# Channel.net
KiCad netlist of a schematic drawn in Altium Designer
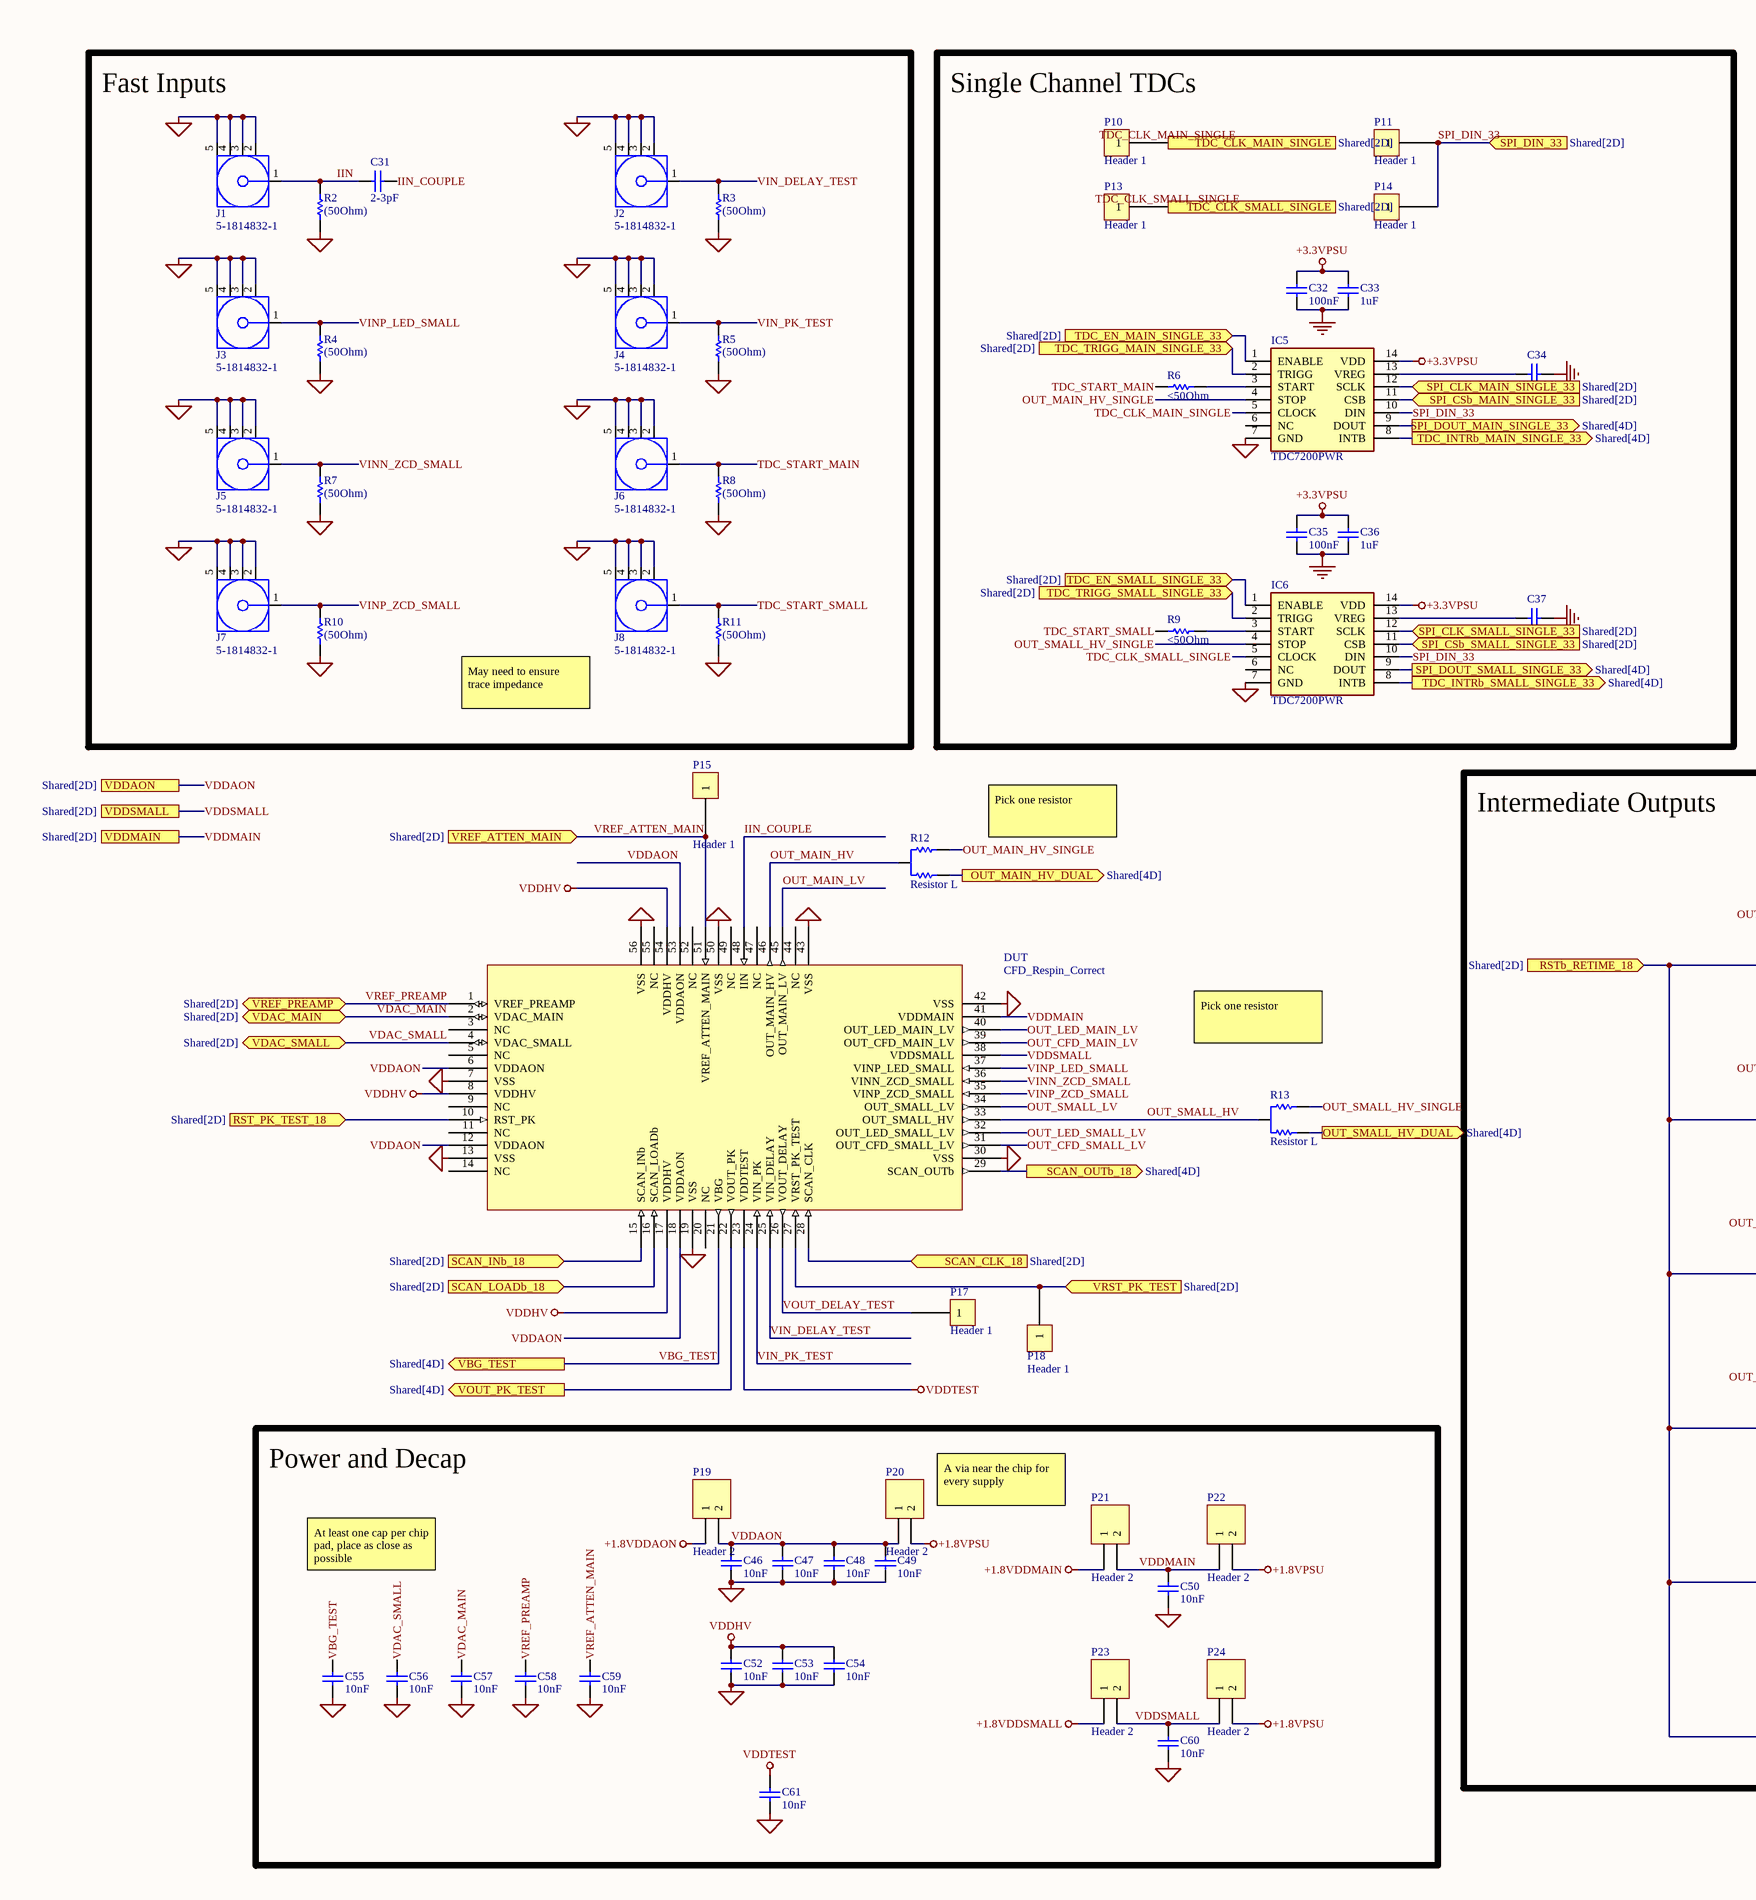
[diagram p0: Channel.SchDoc, left]
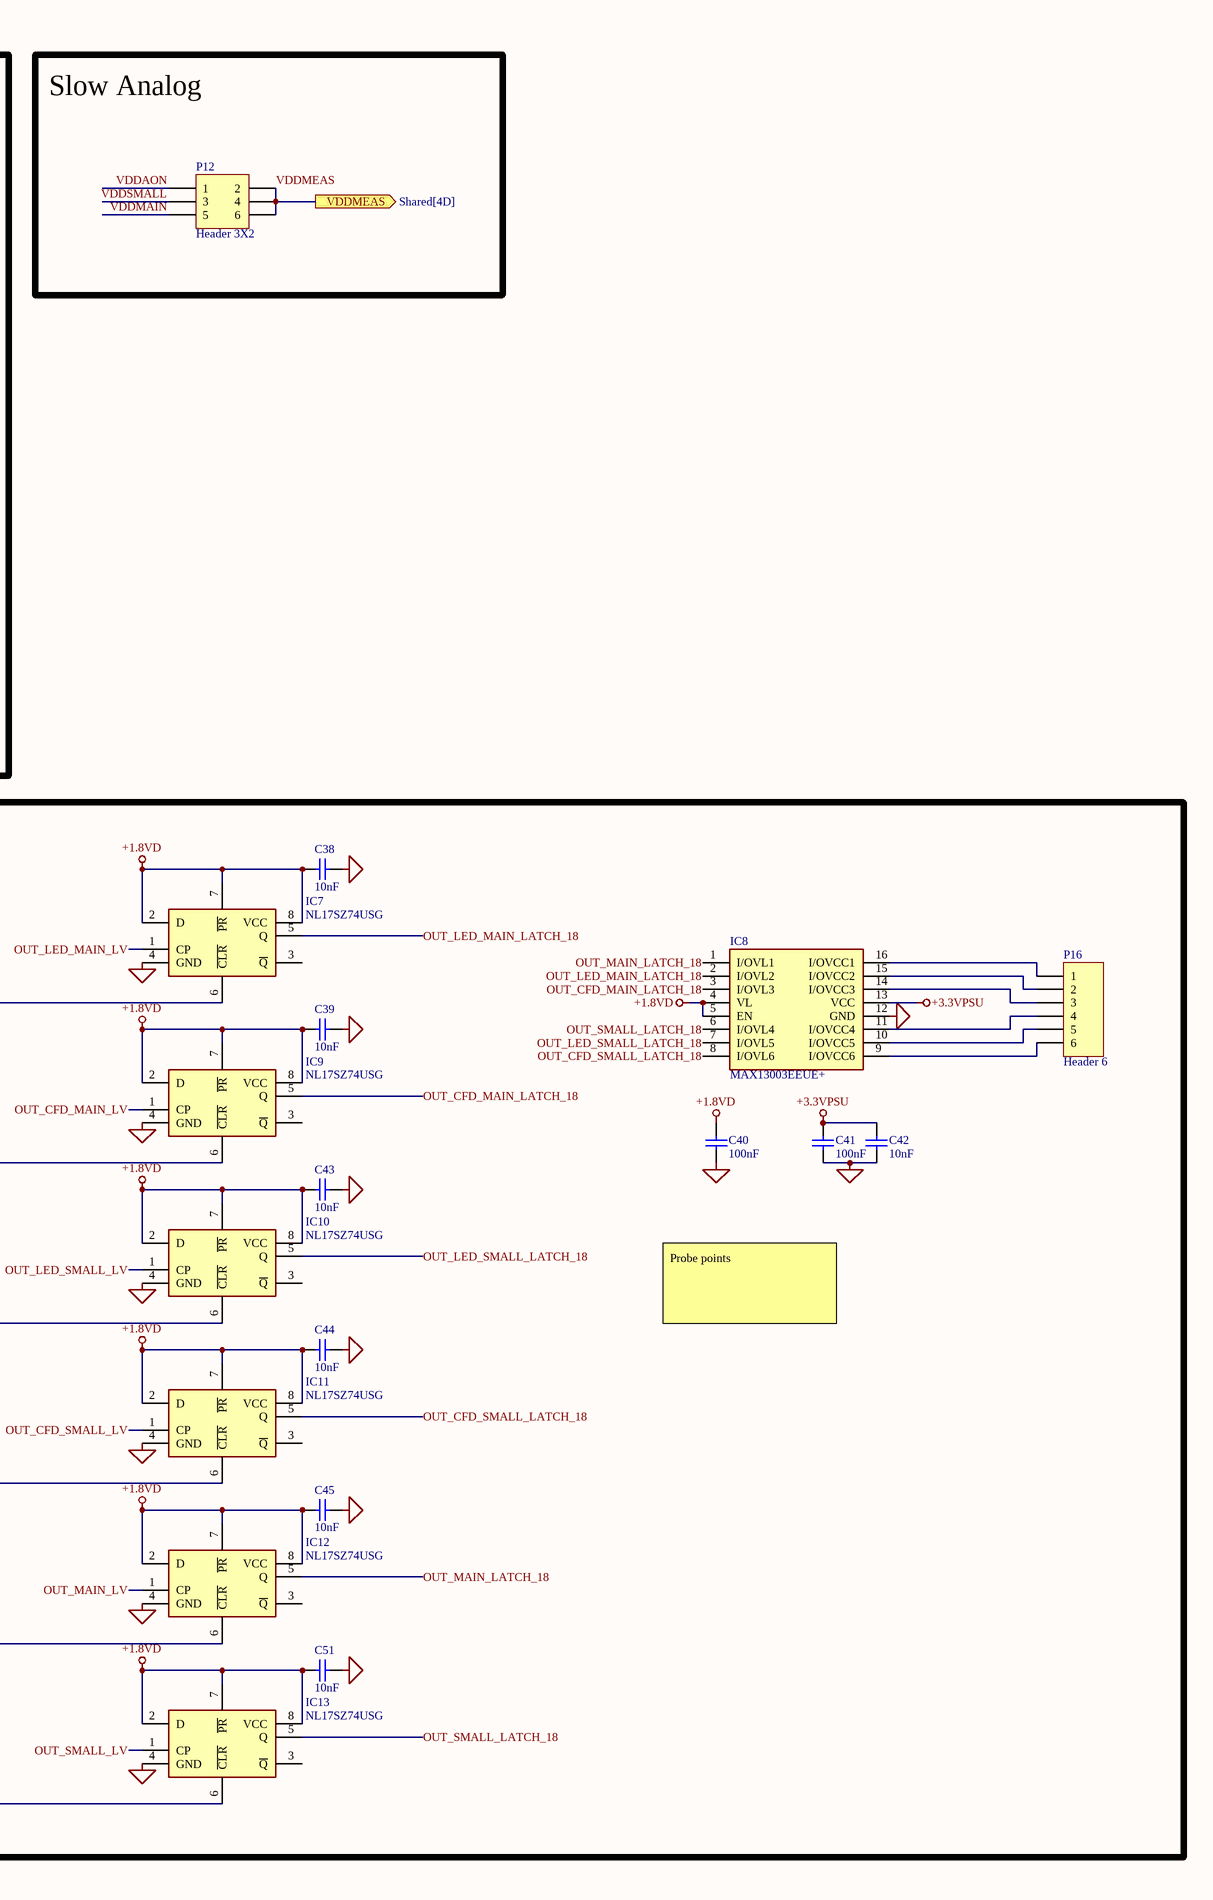
[diagram p1: Channel.SchDoc, right]

(export (version "E")
  (design (tool "Eeschema 10.0.6"))
  (components
    (comp (ref "C31")
      (value "2-3pF")
      (footprint "CAPC1608X90X35ML10T15")
      (description "0603,2-3pF")
      (fields (field (name "MANUFACTURER") "Murata"))
      (libsource (lib "Altium Content Vault") (part "CAP-NP-2"))
    )
    (comp (ref "C32")
      (value "100nF")
      (footprint "CAPC1608X90X35ML10T15")
      (description "0603,100nF")
      (fields (field (name "MANUFACTURER") "Murata"))
      (libsource (lib "Altium Content Vault") (part "CAP-NP-2"))
    )
    (comp (ref "C33")
      (value "1uF")
      (footprint "CAPC1608X90X35ML10T15")
      (description "0603,1uF")
      (fields (field (name "MANUFACTURER") "Murata"))
      (libsource (lib "Altium Content Vault") (part "CAP-NP-2"))
    )
    (comp (ref "C34")
      (value "1uF")
      (footprint "CAPC1608X90X35ML10T15")
      (description "0603,1uF")
      (fields (field (name "MANUFACTURER") "Murata"))
      (libsource (lib "Altium Content Vault") (part "CAP-NP-2"))
    )
    (comp (ref "C35")
      (value "100nF")
      (footprint "CAPC1608X90X35ML10T15")
      (description "0603,100nF")
      (fields (field (name "MANUFACTURER") "Murata"))
      (libsource (lib "Altium Content Vault") (part "CAP-NP-2"))
    )
    (comp (ref "C36")
      (value "1uF")
      (footprint "CAPC1608X90X35ML10T15")
      (description "0603,1uF")
      (fields (field (name "MANUFACTURER") "Murata"))
      (libsource (lib "Altium Content Vault") (part "CAP-NP-2"))
    )
    (comp (ref "C37")
      (value "1uF")
      (footprint "CAPC1608X90X35ML10T15")
      (description "0603,1uF")
      (fields (field (name "MANUFACTURER") "Murata"))
      (libsource (lib "Altium Content Vault") (part "CAP-NP-2"))
    )
    (comp (ref "C38")
      (value "10nF")
      (footprint "CAPC1608X90X35ML10T15")
      (description "0603,10nF")
      (fields (field (name "MANUFACTURER") "Murata"))
      (libsource (lib "Altium Content Vault") (part "CAP-NP-2"))
    )
    (comp (ref "C39")
      (value "10nF")
      (footprint "CAPC1608X90X35ML10T15")
      (description "0603,10nF")
      (fields (field (name "MANUFACTURER") "Murata"))
      (libsource (lib "Altium Content Vault") (part "CAP-NP-2"))
    )
    (comp (ref "C40")
      (value "100nF")
      (footprint "CAPC1608X90X35ML10T15")
      (description "0603,100nF")
      (fields (field (name "MANUFACTURER") "Murata"))
      (libsource (lib "Altium Content Vault") (part "CAP-NP-2"))
    )
    (comp (ref "C41")
      (value "100nF")
      (footprint "CAPC1608X90X35ML10T15")
      (description "0603,100nF")
      (fields (field (name "MANUFACTURER") "Murata"))
      (libsource (lib "Altium Content Vault") (part "CAP-NP-2"))
    )
    (comp (ref "C42")
      (value "10nF")
      (footprint "CAPC1608X90X35ML10T15")
      (description "0603,10nF")
      (fields (field (name "MANUFACTURER") "Murata"))
      (libsource (lib "Altium Content Vault") (part "CAP-NP-2"))
    )
    (comp (ref "C43")
      (value "10nF")
      (footprint "CAPC1608X90X35ML10T15")
      (description "0603,10nF")
      (fields (field (name "MANUFACTURER") "Murata"))
      (libsource (lib "Altium Content Vault") (part "CAP-NP-2"))
    )
    (comp (ref "C44")
      (value "10nF")
      (footprint "CAPC1608X90X35ML10T15")
      (description "0603,10nF")
      (fields (field (name "MANUFACTURER") "Murata"))
      (libsource (lib "Altium Content Vault") (part "CAP-NP-2"))
    )
    (comp (ref "C45")
      (value "10nF")
      (footprint "CAPC1608X90X35ML10T15")
      (description "0603,10nF")
      (fields (field (name "MANUFACTURER") "Murata"))
      (libsource (lib "Altium Content Vault") (part "CAP-NP-2"))
    )
    (comp (ref "C46")
      (value "10nF")
      (footprint "CAPC1608X90X35ML10T15")
      (description "0603,10nF")
      (fields (field (name "MANUFACTURER") "Murata"))
      (libsource (lib "Altium Content Vault") (part "CAP-NP-2"))
    )
    (comp (ref "C47")
      (value "10nF")
      (footprint "CAPC1608X90X35ML10T15")
      (description "0603,10nF")
      (fields (field (name "MANUFACTURER") "Murata"))
      (libsource (lib "Altium Content Vault") (part "CAP-NP-2"))
    )
    (comp (ref "C48")
      (value "10nF")
      (footprint "CAPC1608X90X35ML10T15")
      (description "0603,10nF")
      (fields (field (name "MANUFACTURER") "Murata"))
      (libsource (lib "Altium Content Vault") (part "CAP-NP-2"))
    )
    (comp (ref "C49")
      (value "10nF")
      (footprint "CAPC1608X90X35ML10T15")
      (description "0603,10nF")
      (fields (field (name "MANUFACTURER") "Murata"))
      (libsource (lib "Altium Content Vault") (part "CAP-NP-2"))
    )
    (comp (ref "C50")
      (value "10nF")
      (footprint "CAPC1608X90X35ML10T15")
      (description "0603,10nF")
      (fields (field (name "MANUFACTURER") "Murata"))
      (libsource (lib "Altium Content Vault") (part "CAP-NP-2"))
    )
    (comp (ref "C51")
      (value "10nF")
      (footprint "CAPC1608X90X35ML10T15")
      (description "0603,10nF")
      (fields (field (name "MANUFACTURER") "Murata"))
      (libsource (lib "Altium Content Vault") (part "CAP-NP-2"))
    )
    (comp (ref "C52")
      (value "10nF")
      (footprint "CAPC1608X90X35ML10T15")
      (description "0603,10nF")
      (fields (field (name "MANUFACTURER") "Murata"))
      (libsource (lib "Altium Content Vault") (part "CAP-NP-2"))
    )
    (comp (ref "C53")
      (value "10nF")
      (footprint "CAPC1608X90X35ML10T15")
      (description "0603,10nF")
      (fields (field (name "MANUFACTURER") "Murata"))
      (libsource (lib "Altium Content Vault") (part "CAP-NP-2"))
    )
    (comp (ref "C54")
      (value "10nF")
      (footprint "CAPC1608X90X35ML10T15")
      (description "0603,10nF")
      (fields (field (name "MANUFACTURER") "Murata"))
      (libsource (lib "Altium Content Vault") (part "CAP-NP-2"))
    )
    (comp (ref "C55")
      (value "10nF")
      (footprint "CAPC1608X90X35ML10T15")
      (description "0603,10nF")
      (fields (field (name "MANUFACTURER") "Murata"))
      (libsource (lib "Altium Content Vault") (part "CAP-NP-2"))
    )
    (comp (ref "C56")
      (value "10nF")
      (footprint "CAPC1608X90X35ML10T15")
      (description "0603,10nF")
      (fields (field (name "MANUFACTURER") "Murata"))
      (libsource (lib "Altium Content Vault") (part "CAP-NP-2"))
    )
    (comp (ref "C57")
      (value "10nF")
      (footprint "CAPC1608X90X35ML10T15")
      (description "0603,10nF")
      (fields (field (name "MANUFACTURER") "Murata"))
      (libsource (lib "Altium Content Vault") (part "CAP-NP-2"))
    )
    (comp (ref "C58")
      (value "10nF")
      (footprint "CAPC1608X90X35ML10T15")
      (description "0603,10nF")
      (fields (field (name "MANUFACTURER") "Murata"))
      (libsource (lib "Altium Content Vault") (part "CAP-NP-2"))
    )
    (comp (ref "C59")
      (value "10nF")
      (footprint "CAPC1608X90X35ML10T15")
      (description "0603,10nF")
      (fields (field (name "MANUFACTURER") "Murata"))
      (libsource (lib "Altium Content Vault") (part "CAP-NP-2"))
    )
    (comp (ref "C60")
      (value "10nF")
      (footprint "CAPC1608X90X35ML10T15")
      (description "0603,10nF")
      (fields (field (name "MANUFACTURER") "Murata"))
      (libsource (lib "Altium Content Vault") (part "CAP-NP-2"))
    )
    (comp (ref "C61")
      (value "10nF")
      (footprint "CAPC1608X90X35ML10T15")
      (description "0603,10nF")
      (fields (field (name "MANUFACTURER") "Murata"))
      (libsource (lib "Altium Content Vault") (part "CAP-NP-2"))
    )
    (comp (ref "DUT")
      (value "CFD_Respin_Correct")
      (footprint "QFN50P800X800X80_HS-57N_WIDEVIAS")
      (libsource (lib "intlib") (part "CFD_Respin_Correct"))
    )
    (comp (ref "IC5")
      (value "TDC7200PWR")
      (footprint "SamacSys:SOP65P640X120-14N")
      (description "Integrated Circuit")
      (libsource (lib "*") (part "TDC7200PWR"))
    )
    (comp (ref "IC6")
      (value "TDC7200PWR")
      (footprint "SamacSys:SOP65P640X120-14N")
      (description "Integrated Circuit")
      (libsource (lib "*") (part "TDC7200PWR"))
    )
    (comp (ref "IC7")
      (value "NL17SZ74USG")
      (footprint "SamacSys:SOP50P310X90-8N")
      (description "Flip Flops 1.65-5.5V CMOS Single D-Type")
      (libsource (lib "SamacSys") (part "NL17SZ74USG"))
    )
    (comp (ref "IC8")
      (value "MAX13003EEUE+")
      (footprint "SamacSys:SOP65P640X110-16N")
      (description "Integrated Circuit")
      (libsource (lib "*") (part "MAX13003EEUE+"))
    )
    (comp (ref "IC9")
      (value "NL17SZ74USG")
      (footprint "SamacSys:SOP50P310X90-8N")
      (description "Flip Flops 1.65-5.5V CMOS Single D-Type")
      (libsource (lib "SamacSys") (part "NL17SZ74USG"))
    )
    (comp (ref "IC10")
      (value "NL17SZ74USG")
      (footprint "SamacSys:SOP50P310X90-8N")
      (description "Flip Flops 1.65-5.5V CMOS Single D-Type")
      (libsource (lib "SamacSys") (part "NL17SZ74USG"))
    )
    (comp (ref "IC11")
      (value "NL17SZ74USG")
      (footprint "SamacSys:SOP50P310X90-8N")
      (description "Flip Flops 1.65-5.5V CMOS Single D-Type")
      (libsource (lib "SamacSys") (part "NL17SZ74USG"))
    )
    (comp (ref "IC12")
      (value "NL17SZ74USG")
      (footprint "SamacSys:SOP50P310X90-8N")
      (description "Flip Flops 1.65-5.5V CMOS Single D-Type")
      (libsource (lib "SamacSys") (part "NL17SZ74USG"))
    )
    (comp (ref "IC13")
      (value "NL17SZ74USG")
      (footprint "SamacSys:SOP50P310X90-8N")
      (description "Flip Flops 1.65-5.5V CMOS Single D-Type")
      (libsource (lib "SamacSys") (part "NL17SZ74USG"))
    )
    (comp (ref "J1")
      (value "5-1814832-1")
      (footprint "TECO-5-1814832-1_V")
      (fields (field (name "MANUFACTURER") "TE Connectivity"))
      (libsource (lib "Altium Content Vault") (part "CN-S-4F-RF5"))
    )
    (comp (ref "J2")
      (value "5-1814832-1")
      (footprint "TECO-5-1814832-1_V")
      (fields (field (name "MANUFACTURER") "TE Connectivity"))
      (libsource (lib "Altium Content Vault") (part "CN-S-4F-RF5"))
    )
    (comp (ref "J3")
      (value "5-1814832-1")
      (footprint "TECO-5-1814832-1_V")
      (fields (field (name "MANUFACTURER") "TE Connectivity"))
      (libsource (lib "Altium Content Vault") (part "CN-S-4F-RF5"))
    )
    (comp (ref "J4")
      (value "5-1814832-1")
      (footprint "TECO-5-1814832-1_V")
      (fields (field (name "MANUFACTURER") "TE Connectivity"))
      (libsource (lib "Altium Content Vault") (part "CN-S-4F-RF5"))
    )
    (comp (ref "J5")
      (value "5-1814832-1")
      (footprint "TECO-5-1814832-1_V")
      (fields (field (name "MANUFACTURER") "TE Connectivity"))
      (libsource (lib "Altium Content Vault") (part "CN-S-4F-RF5"))
    )
    (comp (ref "J6")
      (value "5-1814832-1")
      (footprint "TECO-5-1814832-1_V")
      (fields (field (name "MANUFACTURER") "TE Connectivity"))
      (libsource (lib "Altium Content Vault") (part "CN-S-4F-RF5"))
    )
    (comp (ref "J7")
      (value "5-1814832-1")
      (footprint "TECO-5-1814832-1_V")
      (fields (field (name "MANUFACTURER") "TE Connectivity"))
      (libsource (lib "Altium Content Vault") (part "CN-S-4F-RF5"))
    )
    (comp (ref "J8")
      (value "5-1814832-1")
      (footprint "TECO-5-1814832-1_V")
      (fields (field (name "MANUFACTURER") "TE Connectivity"))
      (libsource (lib "Altium Content Vault") (part "CN-S-4F-RF5"))
    )
    (comp (ref "P10") (value "Header 1") (footprint "Header1") (libsource (lib "") (part "Header 1_1")))
    (comp (ref "P11") (value "Header 1") (footprint "Header1") (libsource (lib "") (part "Header 1_1")))
    (comp (ref "P12")
      (value "Header 3X2")
      (footprint "HDR2X3")
      (description "Header, 3-Pin, Dual row")
      (fields (field (name "PUBLISHER") "Altium Limited"))
      (libsource (lib "Miscellaneous Connectors") (part "Header 3X2"))
    )
    (comp (ref "P13") (value "Header 1") (footprint "Header1") (libsource (lib "") (part "Header 1_1")))
    (comp (ref "P14") (value "Header 1") (footprint "Header1") (libsource (lib "") (part "Header 1_1")))
    (comp (ref "P15") (value "Header 1") (footprint "Header1") (libsource (lib "") (part "Header 1_3")))
    (comp (ref "P16")
      (value "Header 6")
      (footprint "HDR1X6")
      (description "Header, 6-Pin")
      (fields (field (name "PUBLISHER") "Altium Limited"))
      (libsource (lib "Miscellaneous Connectors") (part "Header 6"))
    )
    (comp (ref "P17") (value "Header 1") (footprint "Header1") (libsource (lib "") (part "Header 1_2")))
    (comp (ref "P18") (value "Header 1") (footprint "Header1") (libsource (lib "intlib") (part "Header 1")))
    (comp (ref "P19")
      (value "Header 2")
      (footprint "HDR1X2")
      (description "Header, 2-Pin")
      (fields (field (name "PUBLISHER") "Altium Limited"))
      (libsource (lib "Miscellaneous Connectors") (part "Header 2"))
    )
    (comp (ref "P20")
      (value "Header 2")
      (footprint "HDR1X2")
      (description "Header, 2-Pin")
      (fields (field (name "PUBLISHER") "Altium Limited"))
      (libsource (lib "Miscellaneous Connectors") (part "Header 2"))
    )
    (comp (ref "P21")
      (value "Header 2")
      (footprint "HDR1X2")
      (description "Header, 2-Pin")
      (fields (field (name "PUBLISHER") "Altium Limited"))
      (libsource (lib "Miscellaneous Connectors") (part "Header 2"))
    )
    (comp (ref "P22")
      (value "Header 2")
      (footprint "HDR1X2")
      (description "Header, 2-Pin")
      (fields (field (name "PUBLISHER") "Altium Limited"))
      (libsource (lib "Miscellaneous Connectors") (part "Header 2"))
    )
    (comp (ref "P23")
      (value "Header 2")
      (footprint "HDR1X2")
      (description "Header, 2-Pin")
      (fields (field (name "PUBLISHER") "Altium Limited"))
      (libsource (lib "Miscellaneous Connectors") (part "Header 2"))
    )
    (comp (ref "P24")
      (value "Header 2")
      (footprint "HDR1X2")
      (description "Header, 2-Pin")
      (fields (field (name "PUBLISHER") "Altium Limited"))
      (libsource (lib "Miscellaneous Connectors") (part "Header 2"))
    )
    (comp (ref "R2")
      (value "(50Ohm)")
      (footprint "RESC1609X50X30NL8T20")
      (description "0603,(50Ohm),Do Not Populate")
      (fields (field (name "MANUFACTURER") "Vishay Semiconductor"))
      (libsource (lib "Altium Content Vault") (part "RES-2"))
    )
    (comp (ref "R3")
      (value "(50Ohm)")
      (footprint "RESC1609X50X30NL8T20")
      (description "0603,(50Ohm),Do Not Populate")
      (fields (field (name "MANUFACTURER") "Vishay Semiconductor"))
      (libsource (lib "Altium Content Vault") (part "RES-2"))
    )
    (comp (ref "R4")
      (value "(50Ohm)")
      (footprint "RESC1609X50X30NL8T20")
      (description "0603,(50Ohm),Do Not Populate")
      (fields (field (name "MANUFACTURER") "Vishay Semiconductor"))
      (libsource (lib "Altium Content Vault") (part "RES-2"))
    )
    (comp (ref "R5")
      (value "(50Ohm)")
      (footprint "RESC1609X50X30NL8T20")
      (description "0603,(50Ohm),Do Not Populate")
      (fields (field (name "MANUFACTURER") "Vishay Semiconductor"))
      (libsource (lib "Altium Content Vault") (part "RES-2"))
    )
    (comp (ref "R6")
      (value "<50Ohm")
      (footprint "RESC1609X50X30NL8T20")
      (description "0603,<50Ohm")
      (fields (field (name "MANUFACTURER") "Vishay Semiconductor"))
      (libsource (lib "Altium Content Vault") (part "RES-2"))
    )
    (comp (ref "R7")
      (value "(50Ohm)")
      (footprint "RESC1609X50X30NL8T20")
      (description "0603,(50Ohm),Do Not Populate")
      (fields (field (name "MANUFACTURER") "Vishay Semiconductor"))
      (libsource (lib "Altium Content Vault") (part "RES-2"))
    )
    (comp (ref "R8")
      (value "(50Ohm)")
      (footprint "RESC1609X50X30NL8T20")
      (description "0603,(50Ohm),Do Not Populate")
      (fields (field (name "MANUFACTURER") "Vishay Semiconductor"))
      (libsource (lib "Altium Content Vault") (part "RES-2"))
    )
    (comp (ref "R9")
      (value "<50Ohm")
      (footprint "RESC1609X50X30NL8T20")
      (description "0603,<50Ohm")
      (fields (field (name "MANUFACTURER") "Vishay Semiconductor"))
      (libsource (lib "Altium Content Vault") (part "RES-2"))
    )
    (comp (ref "R10")
      (value "(50Ohm)")
      (footprint "RESC1609X50X30NL8T20")
      (description "0603,(50Ohm),Do Not Populate")
      (fields (field (name "MANUFACTURER") "Vishay Semiconductor"))
      (libsource (lib "Altium Content Vault") (part "RES-2"))
    )
    (comp (ref "R11")
      (value "(50Ohm)")
      (footprint "RESC1609X50X30NL8T20")
      (description "0603,(50Ohm),Do Not Populate")
      (fields (field (name "MANUFACTURER") "Vishay Semiconductor"))
      (libsource (lib "Altium Content Vault") (part "RES-2"))
    )
    (comp (ref "R12")
      (value "Resistor L")
      (footprint "RESL")
      (description "Pick one 0603,0Ohm")
      (libsource (lib "intlib") (part "Resistor L"))
    )
    (comp (ref "R13")
      (value "Resistor L")
      (footprint "RESL")
      (description "Pick one 0603,0Ohm")
      (libsource (lib "intlib") (part "Resistor L"))
    )
  )
  (nets
    (net (code "1") (name "+1.8VD") (class "Default")
      (node (ref "C38") (pin "2") (pinfunction "2_2") (pintype "passive"))
      (node (ref "C39") (pin "2") (pinfunction "2_2") (pintype "passive"))
      (node (ref "C40") (pin "2") (pinfunction "2_2") (pintype "passive"))
      (node (ref "C43") (pin "2") (pinfunction "2_2") (pintype "passive"))
      (node (ref "C44") (pin "2") (pinfunction "2_2") (pintype "passive"))
      (node (ref "C45") (pin "2") (pinfunction "2_2") (pintype "passive"))
      (node (ref "C51") (pin "2") (pinfunction "2_2") (pintype "passive"))
      (node (ref "IC10") (pin "2") (pinfunction "D_2") (pintype "passive"))
      (node (ref "IC10") (pin "7") (pinfunction "~{PR}_7") (pintype "passive"))
      (node (ref "IC10") (pin "8") (pinfunction "VCC_8") (pintype "passive"))
      (node (ref "IC11") (pin "2") (pinfunction "D_2") (pintype "passive"))
      (node (ref "IC11") (pin "7") (pinfunction "~{PR}_7") (pintype "passive"))
      (node (ref "IC11") (pin "8") (pinfunction "VCC_8") (pintype "passive"))
      (node (ref "IC12") (pin "2") (pinfunction "D_2") (pintype "passive"))
      (node (ref "IC12") (pin "7") (pinfunction "~{PR}_7") (pintype "passive"))
      (node (ref "IC12") (pin "8") (pinfunction "VCC_8") (pintype "passive"))
      (node (ref "IC13") (pin "2") (pinfunction "D_2") (pintype "passive"))
      (node (ref "IC13") (pin "7") (pinfunction "~{PR}_7") (pintype "passive"))
      (node (ref "IC13") (pin "8") (pinfunction "VCC_8") (pintype "passive"))
      (node (ref "IC7") (pin "2") (pinfunction "D_2") (pintype "passive"))
      (node (ref "IC7") (pin "7") (pinfunction "~{PR}_7") (pintype "passive"))
      (node (ref "IC7") (pin "8") (pinfunction "VCC_8") (pintype "passive"))
      (node (ref "IC8") (pin "4") (pinfunction "VL_4") (pintype "passive"))
      (node (ref "IC8") (pin "5") (pinfunction "EN_5") (pintype "passive"))
      (node (ref "IC9") (pin "2") (pinfunction "D_2") (pintype "passive"))
      (node (ref "IC9") (pin "7") (pinfunction "~{PR}_7") (pintype "passive"))
      (node (ref "IC9") (pin "8") (pinfunction "VCC_8") (pintype "passive"))
    )
    (net (code "2") (name "+1.8VDDAON") (class "Default")
      (node (ref "P19") (pin "1") (pinfunction "1_1") (pintype "passive"))
    )
    (net (code "3") (name "+1.8VDDMAIN") (class "Default")
      (node (ref "P21") (pin "1") (pinfunction "1_1") (pintype "passive"))
    )
    (net (code "4") (name "+1.8VDDSMALL") (class "Default")
      (node (ref "P23") (pin "1") (pinfunction "1_1") (pintype "passive"))
    )
    (net (code "5") (name "+1.8VPSU") (class "Default")
      (node (ref "P20") (pin "2") (pinfunction "2_2") (pintype "passive"))
      (node (ref "P22") (pin "2") (pinfunction "2_2") (pintype "passive"))
      (node (ref "P24") (pin "2") (pinfunction "2_2") (pintype "passive"))
    )
    (net (code "6") (name "+3.3VPSU") (class "Default")
      (node (ref "C32") (pin "1") (pinfunction "1_1") (pintype "passive"))
      (node (ref "C33") (pin "1") (pinfunction "1_1") (pintype "passive"))
      (node (ref "C35") (pin "1") (pinfunction "1_1") (pintype "passive"))
      (node (ref "C36") (pin "1") (pinfunction "1_1") (pintype "passive"))
      (node (ref "C41") (pin "2") (pinfunction "2_2") (pintype "passive"))
      (node (ref "C42") (pin "2") (pinfunction "2_2") (pintype "passive"))
      (node (ref "IC5") (pin "14") (pinfunction "VDD_14") (pintype "passive"))
      (node (ref "IC6") (pin "14") (pinfunction "VDD_14") (pintype "passive"))
      (node (ref "IC8") (pin "13") (pinfunction "VCC_13") (pintype "passive"))
    )
    (net (code "7") (name "/IIN") (class "Default")
      (node (ref "C31") (pin "1") (pinfunction "1_1") (pintype "passive"))
      (node (ref "J1") (pin "1") (pinfunction "1_1") (pintype "passive"))
      (node (ref "R2") (pin "2") (pinfunction "2_2") (pintype "passive"))
    )
    (net (code "8") (name "/IIN_COUPLE") (class "Default")
      (node (ref "C31") (pin "2") (pinfunction "2_2") (pintype "passive"))
      (node (ref "DUT") (pin "48") (pinfunction "IIN_48") (pintype "input"))
    )
    (net (code "9") (name "/OUT_CFD_MAIN_LATCH_18") (class "Default")
      (node (ref "IC8") (pin "3") (pinfunction "I/OVL3_3") (pintype "passive"))
      (node (ref "IC9") (pin "5") (pinfunction "Q_5") (pintype "passive"))
    )
    (net (code "10") (name "/OUT_CFD_MAIN_LV") (class "Default")
      (node (ref "DUT") (pin "39") (pinfunction "OUT_CFD_MAIN_LV_39") (pintype "output"))
      (node (ref "IC9") (pin "1") (pinfunction "CP_1") (pintype "passive"))
    )
    (net (code "11") (name "/OUT_CFD_SMALL_LATCH_18") (class "Default")
      (node (ref "IC11") (pin "5") (pinfunction "Q_5") (pintype "passive"))
      (node (ref "IC8") (pin "8") (pinfunction "I/OVL6_8") (pintype "passive"))
    )
    (net (code "12") (name "/OUT_CFD_SMALL_LV") (class "Default")
      (node (ref "DUT") (pin "31") (pinfunction "OUT_CFD_SMALL_LV_31") (pintype "output"))
      (node (ref "IC11") (pin "1") (pinfunction "CP_1") (pintype "passive"))
    )
    (net (code "13") (name "/OUT_LED_MAIN_LATCH_18") (class "Default")
      (node (ref "IC7") (pin "5") (pinfunction "Q_5") (pintype "passive"))
      (node (ref "IC8") (pin "2") (pinfunction "I/OVL2_2") (pintype "passive"))
    )
    (net (code "14") (name "/OUT_LED_MAIN_LV") (class "Default")
      (node (ref "DUT") (pin "40") (pinfunction "OUT_LED_MAIN_LV_40") (pintype "output"))
      (node (ref "IC7") (pin "1") (pinfunction "CP_1") (pintype "passive"))
    )
    (net (code "15") (name "/OUT_LED_SMALL_LATCH_18") (class "Default")
      (node (ref "IC10") (pin "5") (pinfunction "Q_5") (pintype "passive"))
      (node (ref "IC8") (pin "7") (pinfunction "I/OVL5_7") (pintype "passive"))
    )
    (net (code "16") (name "/OUT_LED_SMALL_LV") (class "Default")
      (node (ref "DUT") (pin "32") (pinfunction "OUT_LED_SMALL_LV_32") (pintype "output"))
      (node (ref "IC10") (pin "1") (pinfunction "CP_1") (pintype "passive"))
    )
    (net (code "17") (name "/OUT_MAIN_HV") (class "Default")
      (node (ref "DUT") (pin "46") (pinfunction "OUT_MAIN_HV_46") (pintype "output"))
      (node (ref "R12") (pin "1") (pinfunction "1_1") (pintype "passive"))
    )
    (net (code "18") (name "/OUT_MAIN_HV_DUAL") (class "Default")
      (node (ref "R12") (pin "2") (pinfunction "2_2") (pintype "passive"))
    )
    (net (code "19") (name "/OUT_MAIN_HV_SINGLE") (class "Default")
      (node (ref "IC5") (pin "4") (pinfunction "STOP_4") (pintype "passive"))
      (node (ref "R12") (pin "3") (pinfunction "3_3") (pintype "passive"))
    )
    (net (code "20") (name "/OUT_MAIN_LATCH_18") (class "Default")
      (node (ref "IC12") (pin "5") (pinfunction "Q_5") (pintype "passive"))
      (node (ref "IC8") (pin "1") (pinfunction "I/OVL1_1") (pintype "passive"))
    )
    (net (code "21") (name "/OUT_MAIN_LV") (class "Default")
      (node (ref "DUT") (pin "45") (pinfunction "OUT_MAIN_LV_45") (pintype "output"))
      (node (ref "IC12") (pin "1") (pinfunction "CP_1") (pintype "passive"))
    )
    (net (code "22") (name "/OUT_SMALL_HV") (class "Default")
      (node (ref "DUT") (pin "33") (pinfunction "OUT_SMALL_HV_33") (pintype "output"))
      (node (ref "R13") (pin "1") (pinfunction "1_1") (pintype "passive"))
    )
    (net (code "23") (name "/OUT_SMALL_HV_DUAL") (class "Default")
      (node (ref "R13") (pin "2") (pinfunction "2_2") (pintype "passive"))
    )
    (net (code "24") (name "/OUT_SMALL_HV_SINGLE") (class "Default")
      (node (ref "IC6") (pin "4") (pinfunction "STOP_4") (pintype "passive"))
      (node (ref "R13") (pin "3") (pinfunction "3_3") (pintype "passive"))
    )
    (net (code "25") (name "/OUT_SMALL_LATCH_18") (class "Default")
      (node (ref "IC13") (pin "5") (pinfunction "Q_5") (pintype "passive"))
      (node (ref "IC8") (pin "6") (pinfunction "I/OVL4_6") (pintype "passive"))
    )
    (net (code "26") (name "/OUT_SMALL_LV") (class "Default")
      (node (ref "DUT") (pin "34") (pinfunction "OUT_SMALL_LV_34") (pintype "output"))
      (node (ref "IC13") (pin "1") (pinfunction "CP_1") (pintype "passive"))
    )
    (net (code "27") (name "/RST_PK_TEST_18") (class "Default")
      (node (ref "DUT") (pin "10") (pinfunction "RST_PK_10") (pintype "input"))
    )
    (net (code "28") (name "/RSTb_RETIME_18") (class "Default")
      (node (ref "IC10") (pin "6") (pinfunction "~{CLR}_6") (pintype "passive"))
      (node (ref "IC11") (pin "6") (pinfunction "~{CLR}_6") (pintype "passive"))
      (node (ref "IC12") (pin "6") (pinfunction "~{CLR}_6") (pintype "passive"))
      (node (ref "IC13") (pin "6") (pinfunction "~{CLR}_6") (pintype "passive"))
      (node (ref "IC7") (pin "6") (pinfunction "~{CLR}_6") (pintype "passive"))
      (node (ref "IC9") (pin "6") (pinfunction "~{CLR}_6") (pintype "passive"))
    )
    (net (code "29") (name "/SCAN_CLK_18") (class "Default")
      (node (ref "DUT") (pin "28") (pinfunction "SCAN_CLK_28") (pintype "input"))
    )
    (net (code "30") (name "/SCAN_INb_18") (class "Default")
      (node (ref "DUT") (pin "15") (pinfunction "SCAN_INb_15") (pintype "input"))
    )
    (net (code "31") (name "/SCAN_LOADb_18") (class "Default")
      (node (ref "DUT") (pin "16") (pinfunction "SCAN_LOADb_16") (pintype "input"))
    )
    (net (code "32") (name "/SCAN_OUTb_18") (class "Default")
      (node (ref "DUT") (pin "29") (pinfunction "SCAN_OUTb_29") (pintype "output"))
    )
    (net (code "33") (name "/SPI_CLK_MAIN_SINGLE_33") (class "Default")
      (node (ref "IC5") (pin "12") (pinfunction "SCLK_12") (pintype "passive"))
    )
    (net (code "34") (name "/SPI_CLK_SMALL_SINGLE_33") (class "Default")
      (node (ref "IC6") (pin "12") (pinfunction "SCLK_12") (pintype "passive"))
    )
    (net (code "35") (name "/SPI_CSb_MAIN_SINGLE_33") (class "Default")
      (node (ref "IC5") (pin "11") (pinfunction "CSB_11") (pintype "passive"))
    )
    (net (code "36") (name "/SPI_CSb_SMALL_SINGLE_33") (class "Default")
      (node (ref "IC6") (pin "11") (pinfunction "CSB_11") (pintype "passive"))
    )
    (net (code "37") (name "/SPI_DIN_33") (class "Default")
      (node (ref "IC5") (pin "10") (pinfunction "DIN_10") (pintype "passive"))
      (node (ref "IC6") (pin "10") (pinfunction "DIN_10") (pintype "passive"))
      (node (ref "P11") (pin "1") (pinfunction "1_1") (pintype "passive"))
      (node (ref "P14") (pin "1") (pinfunction "1_1") (pintype "passive"))
    )
    (net (code "38") (name "/SPI_DOUT_MAIN_SINGLE_33") (class "Default")
      (node (ref "IC5") (pin "9") (pinfunction "DOUT_9") (pintype "passive"))
    )
    (net (code "39") (name "/SPI_DOUT_SMALL_SINGLE_33") (class "Default")
      (node (ref "IC6") (pin "9") (pinfunction "DOUT_9") (pintype "passive"))
    )
    (net (code "40") (name "/TDC_CLK_MAIN_SINGLE") (class "Default")
      (node (ref "IC5") (pin "5") (pinfunction "CLOCK_5") (pintype "passive"))
      (node (ref "P10") (pin "1") (pinfunction "1_1") (pintype "passive"))
    )
    (net (code "41") (name "/TDC_CLK_SMALL_SINGLE") (class "Default")
      (node (ref "IC6") (pin "5") (pinfunction "CLOCK_5") (pintype "passive"))
      (node (ref "P13") (pin "1") (pinfunction "1_1") (pintype "passive"))
    )
    (net (code "42") (name "/TDC_EN_MAIN_SINGLE_33") (class "Default")
      (node (ref "IC5") (pin "1") (pinfunction "ENABLE_1") (pintype "passive"))
    )
    (net (code "43") (name "/TDC_EN_SMALL_SINGLE_33") (class "Default")
      (node (ref "IC6") (pin "1") (pinfunction "ENABLE_1") (pintype "passive"))
    )
    (net (code "44") (name "/TDC_INTRb_MAIN_SINGLE_33") (class "Default")
      (node (ref "IC5") (pin "8") (pinfunction "INTB_8") (pintype "passive"))
    )
    (net (code "45") (name "/TDC_INTRb_SMALL_SINGLE_33") (class "Default")
      (node (ref "IC6") (pin "8") (pinfunction "INTB_8") (pintype "passive"))
    )
    (net (code "46") (name "/TDC_START_MAIN") (class "Default")
      (node (ref "J6") (pin "1") (pinfunction "1_1") (pintype "passive"))
      (node (ref "R6") (pin "1") (pinfunction "1_1") (pintype "passive"))
      (node (ref "R8") (pin "2") (pinfunction "2_2") (pintype "passive"))
    )
    (net (code "47") (name "/TDC_START_SMALL") (class "Default")
      (node (ref "J8") (pin "1") (pinfunction "1_1") (pintype "passive"))
      (node (ref "R11") (pin "2") (pinfunction "2_2") (pintype "passive"))
      (node (ref "R9") (pin "1") (pinfunction "1_1") (pintype "passive"))
    )
    (net (code "48") (name "/TDC_TRIGG_MAIN_SINGLE_33") (class "Default")
      (node (ref "IC5") (pin "2") (pinfunction "TRIGG_2") (pintype "passive"))
    )
    (net (code "49") (name "/TDC_TRIGG_SMALL_SINGLE_33") (class "Default")
      (node (ref "IC6") (pin "2") (pinfunction "TRIGG_2") (pintype "passive"))
    )
    (net (code "50") (name "/VBG_TEST") (class "Default")
      (node (ref "C55") (pin "2") (pinfunction "2_2") (pintype "passive"))
      (node (ref "DUT") (pin "21") (pinfunction "VBG_21") (pintype "output"))
    )
    (net (code "51") (name "/VDAC_MAIN") (class "Default")
      (node (ref "C57") (pin "2") (pinfunction "2_2") (pintype "passive"))
      (node (ref "DUT") (pin "2") (pinfunction "VDAC_MAIN_2") (pintype "bidirectional"))
    )
    (net (code "52") (name "/VDAC_SMALL") (class "Default")
      (node (ref "C56") (pin "2") (pinfunction "2_2") (pintype "passive"))
      (node (ref "DUT") (pin "4") (pinfunction "VDAC_SMALL_4") (pintype "bidirectional"))
    )
    (net (code "53") (name "/VDDAON") (class "Default")
      (node (ref "C46") (pin "2") (pinfunction "2_2") (pintype "passive"))
      (node (ref "C47") (pin "2") (pinfunction "2_2") (pintype "passive"))
      (node (ref "C48") (pin "2") (pinfunction "2_2") (pintype "passive"))
      (node (ref "C49") (pin "2") (pinfunction "2_2") (pintype "passive"))
      (node (ref "DUT") (pin "12") (pinfunction "VDDAON_12") (pintype "power_in"))
      (node (ref "DUT") (pin "18") (pinfunction "VDDAON_18") (pintype "power_in"))
      (node (ref "DUT") (pin "53") (pinfunction "VDDAON_53") (pintype "power_in"))
      (node (ref "DUT") (pin "6") (pinfunction "VDDAON_6") (pintype "power_in"))
      (node (ref "P12") (pin "1") (pinfunction "1_1") (pintype "passive"))
      (node (ref "P19") (pin "2") (pinfunction "2_2") (pintype "passive"))
      (node (ref "P20") (pin "1") (pinfunction "1_1") (pintype "passive"))
    )
    (net (code "54") (name "/VDDMAIN") (class "Default")
      (node (ref "C50") (pin "2") (pinfunction "2_2") (pintype "passive"))
      (node (ref "DUT") (pin "41") (pinfunction "VDDMAIN_41") (pintype "power_in"))
      (node (ref "P12") (pin "5") (pinfunction "5_5") (pintype "passive"))
      (node (ref "P21") (pin "2") (pinfunction "2_2") (pintype "passive"))
      (node (ref "P22") (pin "1") (pinfunction "1_1") (pintype "passive"))
    )
    (net (code "55") (name "/VDDMEAS") (class "Default")
      (node (ref "P12") (pin "2") (pinfunction "2_2") (pintype "passive"))
      (node (ref "P12") (pin "4") (pinfunction "4_4") (pintype "passive"))
      (node (ref "P12") (pin "6") (pinfunction "6_6") (pintype "passive"))
    )
    (net (code "56") (name "/VDDSMALL") (class "Default")
      (node (ref "C60") (pin "2") (pinfunction "2_2") (pintype "passive"))
      (node (ref "DUT") (pin "38") (pinfunction "VDDSMALL_38") (pintype "power_in"))
      (node (ref "P12") (pin "3") (pinfunction "3_3") (pintype "passive"))
      (node (ref "P23") (pin "2") (pinfunction "2_2") (pintype "passive"))
      (node (ref "P24") (pin "1") (pinfunction "1_1") (pintype "passive"))
    )
    (net (code "57") (name "/VINN_ZCD_SMALL") (class "Default")
      (node (ref "DUT") (pin "36") (pinfunction "VINN_ZCD_SMALL_36") (pintype "input"))
      (node (ref "J5") (pin "1") (pinfunction "1_1") (pintype "passive"))
      (node (ref "R7") (pin "2") (pinfunction "2_2") (pintype "passive"))
    )
    (net (code "58") (name "/VINP_LED_SMALL") (class "Default")
      (node (ref "DUT") (pin "37") (pinfunction "VINP_LED_SMALL_37") (pintype "input"))
      (node (ref "J3") (pin "1") (pinfunction "1_1") (pintype "passive"))
      (node (ref "R4") (pin "2") (pinfunction "2_2") (pintype "passive"))
    )
    (net (code "59") (name "/VINP_ZCD_SMALL") (class "Default")
      (node (ref "DUT") (pin "35") (pinfunction "VINP_ZCD_SMALL_35") (pintype "input"))
      (node (ref "J7") (pin "1") (pinfunction "1_1") (pintype "passive"))
      (node (ref "R10") (pin "2") (pinfunction "2_2") (pintype "passive"))
    )
    (net (code "60") (name "/VIN_DELAY_TEST") (class "Default")
      (node (ref "DUT") (pin "25") (pinfunction "VIN_DELAY_25") (pintype "input"))
      (node (ref "J2") (pin "1") (pinfunction "1_1") (pintype "passive"))
      (node (ref "R3") (pin "2") (pinfunction "2_2") (pintype "passive"))
    )
    (net (code "61") (name "/VIN_PK_TEST") (class "Default")
      (node (ref "DUT") (pin "24") (pinfunction "VIN_PK_24") (pintype "input"))
      (node (ref "J4") (pin "1") (pinfunction "1_1") (pintype "passive"))
      (node (ref "R5") (pin "2") (pinfunction "2_2") (pintype "passive"))
    )
    (net (code "62") (name "/VOUT_DELAY_TEST") (class "Default")
      (node (ref "DUT") (pin "26") (pinfunction "VOUT_DELAY_26") (pintype "output"))
      (node (ref "P17") (pin "1") (pinfunction "1_1") (pintype "passive"))
    )
    (net (code "63") (name "/VOUT_PK_TEST") (class "Default")
      (node (ref "DUT") (pin "22") (pinfunction "VOUT_PK_22") (pintype "output"))
    )
    (net (code "64") (name "/VREF_ATTEN_MAIN") (class "Default")
      (node (ref "C59") (pin "2") (pinfunction "2_2") (pintype "passive"))
      (node (ref "DUT") (pin "51") (pinfunction "VREF_ATTEN_MAIN_51") (pintype "input"))
      (node (ref "P15") (pin "1") (pinfunction "1_1") (pintype "passive"))
    )
    (net (code "65") (name "/VREF_PREAMP") (class "Default")
      (node (ref "C58") (pin "2") (pinfunction "2_2") (pintype "passive"))
      (node (ref "DUT") (pin "1") (pinfunction "VREF_PREAMP_1") (pintype "bidirectional"))
    )
    (net (code "66") (name "/VRST_PK_TEST") (class "Default")
      (node (ref "DUT") (pin "27") (pinfunction "VRST_PK_TEST_27") (pintype "input"))
      (node (ref "P18") (pin "1") (pinfunction "1_1") (pintype "passive"))
    )
    (net (code "67") (name "GND") (class "Default")
      (node (ref "C32") (pin "2") (pinfunction "2_2") (pintype "passive"))
      (node (ref "C33") (pin "2") (pinfunction "2_2") (pintype "passive"))
      (node (ref "C34") (pin "2") (pinfunction "2_2") (pintype "passive"))
      (node (ref "C35") (pin "2") (pinfunction "2_2") (pintype "passive"))
      (node (ref "C36") (pin "2") (pinfunction "2_2") (pintype "passive"))
      (node (ref "C37") (pin "2") (pinfunction "2_2") (pintype "passive"))
      (node (ref "C38") (pin "1") (pinfunction "1_1") (pintype "passive"))
      (node (ref "C39") (pin "1") (pinfunction "1_1") (pintype "passive"))
      (node (ref "C40") (pin "1") (pinfunction "1_1") (pintype "passive"))
      (node (ref "C41") (pin "1") (pinfunction "1_1") (pintype "passive"))
      (node (ref "C42") (pin "1") (pinfunction "1_1") (pintype "passive"))
      (node (ref "C43") (pin "1") (pinfunction "1_1") (pintype "passive"))
      (node (ref "C44") (pin "1") (pinfunction "1_1") (pintype "passive"))
      (node (ref "C45") (pin "1") (pinfunction "1_1") (pintype "passive"))
      (node (ref "C46") (pin "1") (pinfunction "1_1") (pintype "passive"))
      (node (ref "C47") (pin "1") (pinfunction "1_1") (pintype "passive"))
      (node (ref "C48") (pin "1") (pinfunction "1_1") (pintype "passive"))
      (node (ref "C49") (pin "1") (pinfunction "1_1") (pintype "passive"))
      (node (ref "C50") (pin "1") (pinfunction "1_1") (pintype "passive"))
      (node (ref "C51") (pin "1") (pinfunction "1_1") (pintype "passive"))
      (node (ref "C52") (pin "1") (pinfunction "1_1") (pintype "passive"))
      (node (ref "C53") (pin "1") (pinfunction "1_1") (pintype "passive"))
      (node (ref "C54") (pin "1") (pinfunction "1_1") (pintype "passive"))
      (node (ref "C55") (pin "1") (pinfunction "1_1") (pintype "passive"))
      (node (ref "C56") (pin "1") (pinfunction "1_1") (pintype "passive"))
      (node (ref "C57") (pin "1") (pinfunction "1_1") (pintype "passive"))
      (node (ref "C58") (pin "1") (pinfunction "1_1") (pintype "passive"))
      (node (ref "C59") (pin "1") (pinfunction "1_1") (pintype "passive"))
      (node (ref "C60") (pin "1") (pinfunction "1_1") (pintype "passive"))
      (node (ref "C61") (pin "1") (pinfunction "1_1") (pintype "passive"))
      (node (ref "DUT") (pin "13") (pinfunction "VSS_13") (pintype "power_in"))
      (node (ref "DUT") (pin "19") (pinfunction "VSS_19") (pintype "power_in"))
      (node (ref "DUT") (pin "30") (pinfunction "VSS_30") (pintype "power_in"))
      (node (ref "DUT") (pin "42") (pinfunction "VSS_42") (pintype "power_in"))
      (node (ref "DUT") (pin "43") (pinfunction "VSS_43") (pintype "power_in"))
      (node (ref "DUT") (pin "50") (pinfunction "VSS_50") (pintype "power_in"))
      (node (ref "DUT") (pin "56") (pinfunction "VSS_56") (pintype "power_in"))
      (node (ref "DUT") (pin "7") (pinfunction "VSS_7") (pintype "power_in"))
      (node (ref "IC10") (pin "4") (pinfunction "GND_4") (pintype "passive"))
      (node (ref "IC11") (pin "4") (pinfunction "GND_4") (pintype "passive"))
      (node (ref "IC12") (pin "4") (pinfunction "GND_4") (pintype "passive"))
      (node (ref "IC13") (pin "4") (pinfunction "GND_4") (pintype "passive"))
      (node (ref "IC5") (pin "7") (pinfunction "GND_7") (pintype "passive"))
      (node (ref "IC6") (pin "7") (pinfunction "GND_7") (pintype "passive"))
      (node (ref "IC7") (pin "4") (pinfunction "GND_4") (pintype "passive"))
      (node (ref "IC8") (pin "12") (pinfunction "GND_12") (pintype "passive"))
      (node (ref "IC9") (pin "4") (pinfunction "GND_4") (pintype "passive"))
      (node (ref "J1") (pin "2") (pinfunction "2_2") (pintype "passive"))
      (node (ref "J1") (pin "3") (pinfunction "3_3") (pintype "passive"))
      (node (ref "J1") (pin "4") (pinfunction "4_4") (pintype "passive"))
      (node (ref "J1") (pin "5") (pinfunction "5_5") (pintype "passive"))
      (node (ref "J2") (pin "2") (pinfunction "2_2") (pintype "passive"))
      (node (ref "J2") (pin "3") (pinfunction "3_3") (pintype "passive"))
      (node (ref "J2") (pin "4") (pinfunction "4_4") (pintype "passive"))
      (node (ref "J2") (pin "5") (pinfunction "5_5") (pintype "passive"))
      (node (ref "J3") (pin "2") (pinfunction "2_2") (pintype "passive"))
      (node (ref "J3") (pin "3") (pinfunction "3_3") (pintype "passive"))
      (node (ref "J3") (pin "4") (pinfunction "4_4") (pintype "passive"))
      (node (ref "J3") (pin "5") (pinfunction "5_5") (pintype "passive"))
      (node (ref "J4") (pin "2") (pinfunction "2_2") (pintype "passive"))
      (node (ref "J4") (pin "3") (pinfunction "3_3") (pintype "passive"))
      (node (ref "J4") (pin "4") (pinfunction "4_4") (pintype "passive"))
      (node (ref "J4") (pin "5") (pinfunction "5_5") (pintype "passive"))
      (node (ref "J5") (pin "2") (pinfunction "2_2") (pintype "passive"))
      (node (ref "J5") (pin "3") (pinfunction "3_3") (pintype "passive"))
      (node (ref "J5") (pin "4") (pinfunction "4_4") (pintype "passive"))
      (node (ref "J5") (pin "5") (pinfunction "5_5") (pintype "passive"))
      (node (ref "J6") (pin "2") (pinfunction "2_2") (pintype "passive"))
      (node (ref "J6") (pin "3") (pinfunction "3_3") (pintype "passive"))
      (node (ref "J6") (pin "4") (pinfunction "4_4") (pintype "passive"))
      (node (ref "J6") (pin "5") (pinfunction "5_5") (pintype "passive"))
      (node (ref "J7") (pin "2") (pinfunction "2_2") (pintype "passive"))
      (node (ref "J7") (pin "3") (pinfunction "3_3") (pintype "passive"))
      (node (ref "J7") (pin "4") (pinfunction "4_4") (pintype "passive"))
      (node (ref "J7") (pin "5") (pinfunction "5_5") (pintype "passive"))
      (node (ref "J8") (pin "2") (pinfunction "2_2") (pintype "passive"))
      (node (ref "J8") (pin "3") (pinfunction "3_3") (pintype "passive"))
      (node (ref "J8") (pin "4") (pinfunction "4_4") (pintype "passive"))
      (node (ref "J8") (pin "5") (pinfunction "5_5") (pintype "passive"))
      (node (ref "R10") (pin "1") (pinfunction "1_1") (pintype "passive"))
      (node (ref "R11") (pin "1") (pinfunction "1_1") (pintype "passive"))
      (node (ref "R2") (pin "1") (pinfunction "1_1") (pintype "passive"))
      (node (ref "R3") (pin "1") (pinfunction "1_1") (pintype "passive"))
      (node (ref "R4") (pin "1") (pinfunction "1_1") (pintype "passive"))
      (node (ref "R5") (pin "1") (pinfunction "1_1") (pintype "passive"))
      (node (ref "R7") (pin "1") (pinfunction "1_1") (pintype "passive"))
      (node (ref "R8") (pin "1") (pinfunction "1_1") (pintype "passive"))
    )
    (net (code "68") (name "Net-(IC5-START)") (class "Default")
      (node (ref "IC5") (pin "3") (pinfunction "START_3") (pintype "passive"))
      (node (ref "R6") (pin "2") (pinfunction "2_2") (pintype "passive"))
    )
    (net (code "69") (name "Net-(IC5-VREG)") (class "Default")
      (node (ref "C34") (pin "1") (pinfunction "1_1") (pintype "passive"))
      (node (ref "IC5") (pin "13") (pinfunction "VREG_13") (pintype "passive"))
    )
    (net (code "70") (name "Net-(IC6-START)") (class "Default")
      (node (ref "IC6") (pin "3") (pinfunction "START_3") (pintype "passive"))
      (node (ref "R9") (pin "2") (pinfunction "2_2") (pintype "passive"))
    )
    (net (code "71") (name "Net-(IC6-VREG)") (class "Default")
      (node (ref "C37") (pin "1") (pinfunction "1_1") (pintype "passive"))
      (node (ref "IC6") (pin "13") (pinfunction "VREG_13") (pintype "passive"))
    )
    (net (code "72") (name "Net-(IC8-I{slash}OVCC1)") (class "Default")
      (node (ref "IC8") (pin "16") (pinfunction "I/OVCC1_16") (pintype "passive"))
      (node (ref "P16") (pin "1") (pinfunction "1_1") (pintype "passive"))
    )
    (net (code "73") (name "Net-(IC8-I{slash}OVCC2)") (class "Default")
      (node (ref "IC8") (pin "15") (pinfunction "I/OVCC2_15") (pintype "passive"))
      (node (ref "P16") (pin "2") (pinfunction "2_2") (pintype "passive"))
    )
    (net (code "74") (name "Net-(IC8-I{slash}OVCC3)") (class "Default")
      (node (ref "IC8") (pin "14") (pinfunction "I/OVCC3_14") (pintype "passive"))
      (node (ref "P16") (pin "3") (pinfunction "3_3") (pintype "passive"))
    )
    (net (code "75") (name "Net-(IC8-I{slash}OVCC4)") (class "Default")
      (node (ref "IC8") (pin "11") (pinfunction "I/OVCC4_11") (pintype "passive"))
      (node (ref "P16") (pin "4") (pinfunction "4_4") (pintype "passive"))
    )
    (net (code "76") (name "Net-(IC8-I{slash}OVCC5)") (class "Default")
      (node (ref "IC8") (pin "10") (pinfunction "I/OVCC5_10") (pintype "passive"))
      (node (ref "P16") (pin "5") (pinfunction "5_5") (pintype "passive"))
    )
    (net (code "77") (name "Net-(IC8-I{slash}OVCC6)") (class "Default")
      (node (ref "IC8") (pin "9") (pinfunction "I/OVCC6_9") (pintype "passive"))
      (node (ref "P16") (pin "6") (pinfunction "6_6") (pintype "passive"))
    )
    (net (code "78") (name "VDDHV") (class "Default")
      (node (ref "C52") (pin "2") (pinfunction "2_2") (pintype "passive"))
      (node (ref "C53") (pin "2") (pinfunction "2_2") (pintype "passive"))
      (node (ref "C54") (pin "2") (pinfunction "2_2") (pintype "passive"))
      (node (ref "DUT") (pin "17") (pinfunction "VDDHV_17") (pintype "power_in"))
      (node (ref "DUT") (pin "54") (pinfunction "VDDHV_54") (pintype "power_in"))
      (node (ref "DUT") (pin "8") (pinfunction "VDDHV_8") (pintype "power_in"))
    )
    (net (code "79") (name "VDDTEST") (class "Default")
      (node (ref "C61") (pin "2") (pinfunction "2_2") (pintype "passive"))
      (node (ref "DUT") (pin "23") (pinfunction "VDDTEST_23") (pintype "power_in"))
    )
    (net (code "80") (name "unconnected-(DUT-NC-Pad3)") (class "Default")
      (node (ref "DUT") (pin "3") (pinfunction "NC_3") (pintype "passive"))
    )
    (net (code "81") (name "unconnected-(DUT-NC-Pad5)") (class "Default")
      (node (ref "DUT") (pin "5") (pinfunction "NC_5") (pintype "passive"))
    )
    (net (code "82") (name "unconnected-(DUT-NC-Pad9)") (class "Default")
      (node (ref "DUT") (pin "9") (pinfunction "NC_9") (pintype "passive"))
    )
    (net (code "83") (name "unconnected-(DUT-NC-Pad11)") (class "Default")
      (node (ref "DUT") (pin "11") (pinfunction "NC_11") (pintype "passive"))
    )
    (net (code "84") (name "unconnected-(DUT-NC-Pad14)") (class "Default")
      (node (ref "DUT") (pin "14") (pinfunction "NC_14") (pintype "passive"))
    )
    (net (code "85") (name "unconnected-(DUT-NC-Pad20)") (class "Default")
      (node (ref "DUT") (pin "20") (pinfunction "NC_20") (pintype "passive"))
    )
    (net (code "86") (name "unconnected-(DUT-NC-Pad44)") (class "Default")
      (node (ref "DUT") (pin "44") (pinfunction "NC_44") (pintype "passive"))
    )
    (net (code "87") (name "unconnected-(DUT-NC-Pad47)") (class "Default")
      (node (ref "DUT") (pin "47") (pinfunction "NC_47") (pintype "passive"))
    )
    (net (code "88") (name "unconnected-(DUT-NC-Pad49)") (class "Default")
      (node (ref "DUT") (pin "49") (pinfunction "NC_49") (pintype "passive"))
    )
    (net (code "89") (name "unconnected-(DUT-NC-Pad52)") (class "Default")
      (node (ref "DUT") (pin "52") (pinfunction "NC_52") (pintype "passive"))
    )
    (net (code "90") (name "unconnected-(DUT-NC-Pad55)") (class "Default")
      (node (ref "DUT") (pin "55") (pinfunction "NC_55") (pintype "passive"))
    )
    (net (code "91") (name "unconnected-(IC5-NC-Pad6)") (class "Default")
      (node (ref "IC5") (pin "6") (pinfunction "NC_6") (pintype "passive"))
    )
    (net (code "92") (name "unconnected-(IC6-NC-Pad6)") (class "Default")
      (node (ref "IC6") (pin "6") (pinfunction "NC_6") (pintype "passive"))
    )
    (net (code "93") (name "unconnected-(IC7-~{Q}-Pad3)") (class "Default")
      (node (ref "IC7") (pin "3") (pinfunction "~{Q}_3") (pintype "passive"))
    )
    (net (code "94") (name "unconnected-(IC9-~{Q}-Pad3)") (class "Default")
      (node (ref "IC9") (pin "3") (pinfunction "~{Q}_3") (pintype "passive"))
    )
    (net (code "95") (name "unconnected-(IC10-~{Q}-Pad3)") (class "Default")
      (node (ref "IC10") (pin "3") (pinfunction "~{Q}_3") (pintype "passive"))
    )
    (net (code "96") (name "unconnected-(IC11-~{Q}-Pad3)") (class "Default")
      (node (ref "IC11") (pin "3") (pinfunction "~{Q}_3") (pintype "passive"))
    )
    (net (code "97") (name "unconnected-(IC12-~{Q}-Pad3)") (class "Default")
      (node (ref "IC12") (pin "3") (pinfunction "~{Q}_3") (pintype "passive"))
    )
    (net (code "98") (name "unconnected-(IC13-~{Q}-Pad3)") (class "Default")
      (node (ref "IC13") (pin "3") (pinfunction "~{Q}_3") (pintype "passive"))
    )
  )
)
